# Ex_7_Segment_Display_Common_Cathode.net
KiCad netlist of a schematic drawn in EAGLE
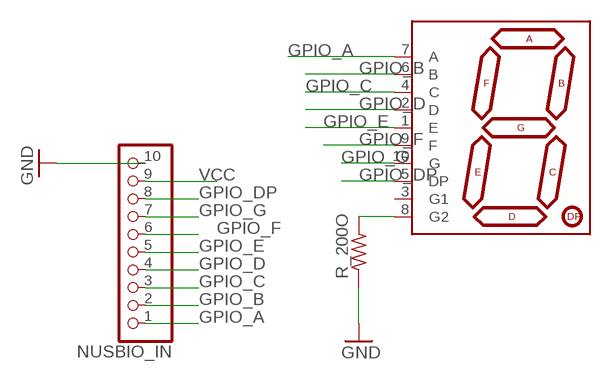
[diagram p0: schematic, sheet 1]

(export (version "E")
  (design (tool "Eeschema 10.0.6"))
  (components
    (comp (ref "NUSBIO_IN")
      (value "PINHD-1X10")
      (footprint "eagle-import:1X10-BIG")
      (libsource (lib "eagle-import") (part "PINHD-1X10"))
    )
    (comp (ref "R_200O")
      (value "R-US_R1206")
      (footprint "eagle-import:R1206")
      (libsource (lib "eagle-import") (part "R-US_R1206"))
    )
    (comp (ref "U$1")
      (value "7-SEGMENT-DISPLAYPTH")
      (footprint "eagle-import:7-SEGMENT-DISPLAY")
      (libsource (lib "eagle-import") (part "7-SEGMENT-DISPLAYPTH"))
    )
  )
  (nets
    (net (code "1") (name "/GPIO_A") (class "Default")
      (node (ref "NUSBIO_IN") (pin "1") (pinfunction "1_1") (pintype "passive"))
      (node (ref "U$1") (pin "7") (pinfunction "A_7") (pintype "bidirectional"))
    )
    (net (code "2") (name "/GPIO_B") (class "Default")
      (node (ref "NUSBIO_IN") (pin "2") (pinfunction "2_2") (pintype "passive"))
      (node (ref "U$1") (pin "6") (pinfunction "B_6") (pintype "bidirectional"))
    )
    (net (code "3") (name "/GPIO_C") (class "Default")
      (node (ref "NUSBIO_IN") (pin "3") (pinfunction "3_3") (pintype "passive"))
      (node (ref "U$1") (pin "4") (pinfunction "C_4") (pintype "bidirectional"))
    )
    (net (code "4") (name "/GPIO_D") (class "Default")
      (node (ref "NUSBIO_IN") (pin "4") (pinfunction "4_4") (pintype "passive"))
      (node (ref "U$1") (pin "2") (pinfunction "D_2") (pintype "bidirectional"))
    )
    (net (code "5") (name "/GPIO_DP") (class "Default")
      (node (ref "NUSBIO_IN") (pin "8") (pinfunction "8_8") (pintype "passive"))
      (node (ref "U$1") (pin "5") (pinfunction "DP_5") (pintype "bidirectional"))
    )
    (net (code "6") (name "/GPIO_E") (class "Default")
      (node (ref "NUSBIO_IN") (pin "5") (pinfunction "5_5") (pintype "passive"))
      (node (ref "U$1") (pin "1") (pinfunction "E_1") (pintype "bidirectional"))
    )
    (net (code "7") (name "/GPIO_F") (class "Default")
      (node (ref "NUSBIO_IN") (pin "6") (pinfunction "6_6") (pintype "passive"))
      (node (ref "U$1") (pin "9") (pinfunction "F_9") (pintype "bidirectional"))
    )
    (net (code "8") (name "/GPIO_G") (class "Default")
      (node (ref "NUSBIO_IN") (pin "7") (pinfunction "7_7") (pintype "passive"))
      (node (ref "U$1") (pin "10") (pinfunction "G_10") (pintype "bidirectional"))
    )
    (net (code "9") (name "/VCC") (class "Default")
      (node (ref "NUSBIO_IN") (pin "9") (pinfunction "9_9") (pintype "passive"))
    )
    (net (code "10") (name "GND") (class "Default")
      (node (ref "NUSBIO_IN") (pin "10") (pinfunction "10_10") (pintype "passive"))
      (node (ref "R_200O") (pin "1") (pinfunction "1_1") (pintype "passive"))
    )
    (net (code "11") (name "Net-(U$1-G2)") (class "Default")
      (node (ref "R_200O") (pin "2") (pinfunction "2_2") (pintype "passive"))
      (node (ref "U$1") (pin "8") (pinfunction "G2_8") (pintype "bidirectional"))
    )
    (net (code "12") (name "unconnected-(U$1-G1-Pad3)") (class "Default")
      (node (ref "U$1") (pin "3") (pinfunction "G1_3") (pintype "bidirectional"))
    )
  )
)
